# PMIC-MX8M.net
KiCad netlist of a schematic drawn in Altium Designer
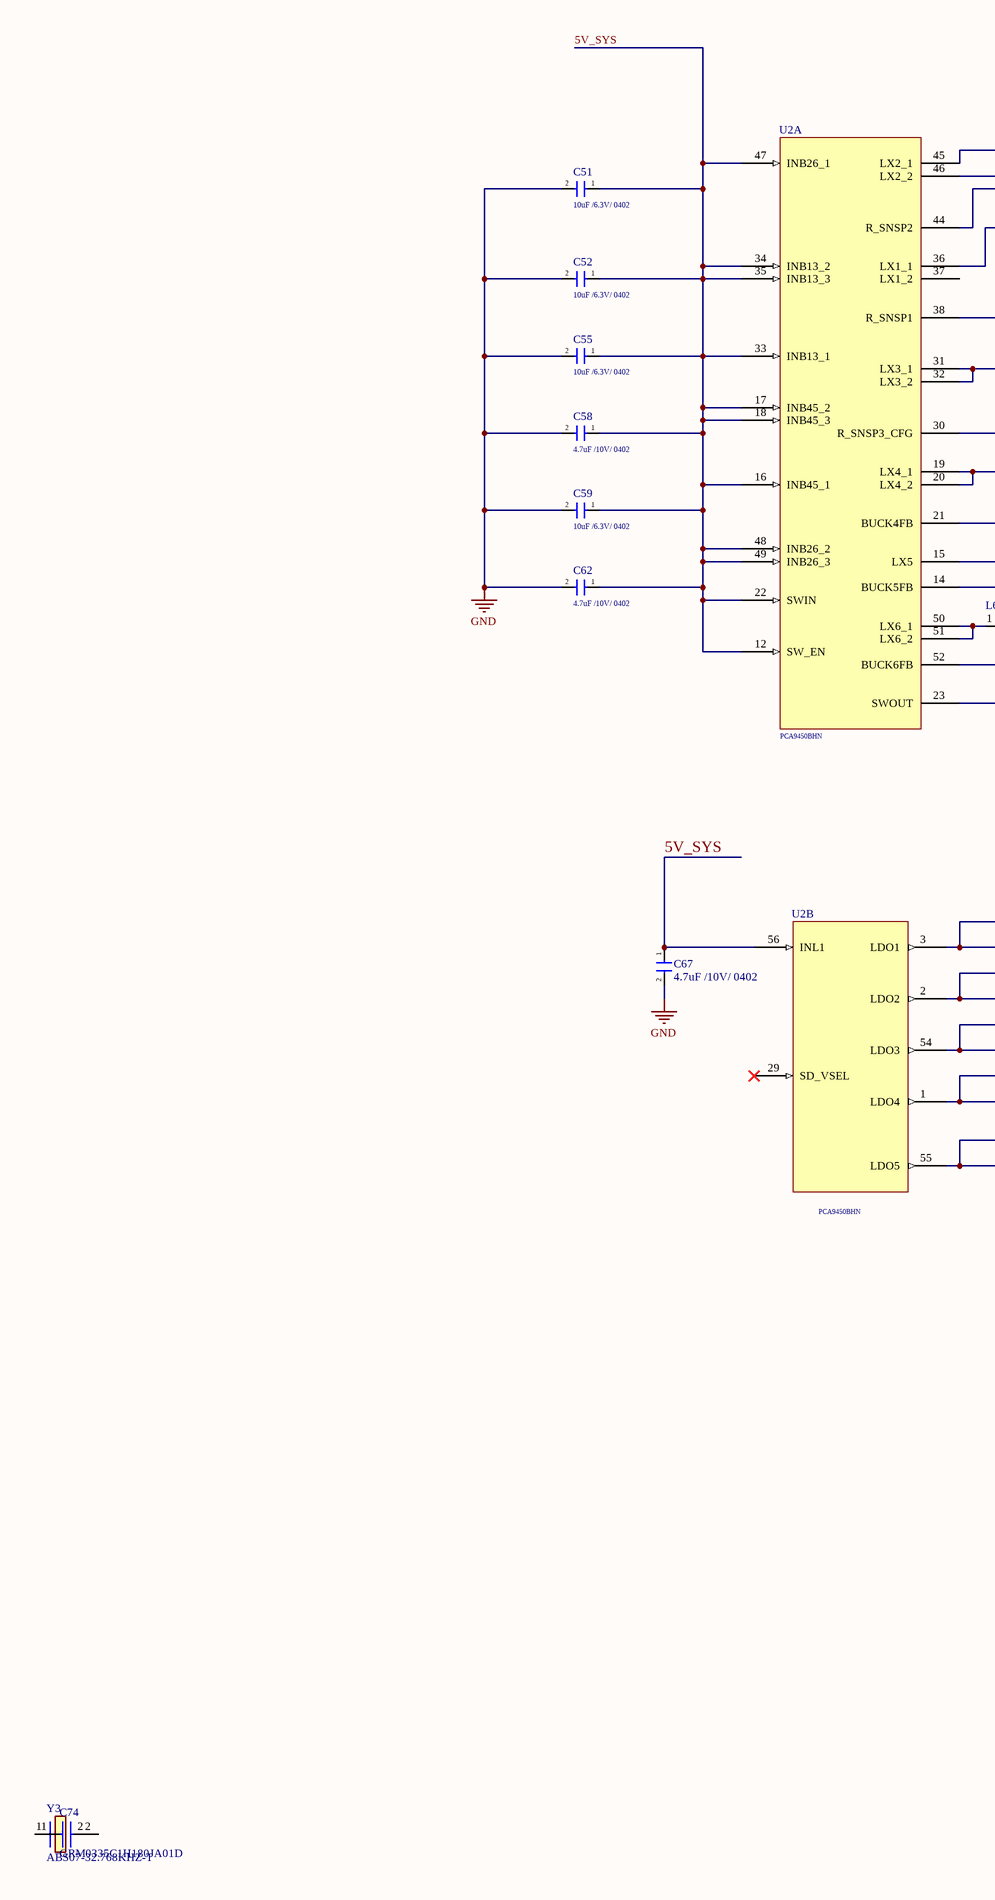
[diagram p0: PMIC-MX8M.SchDoc, left]
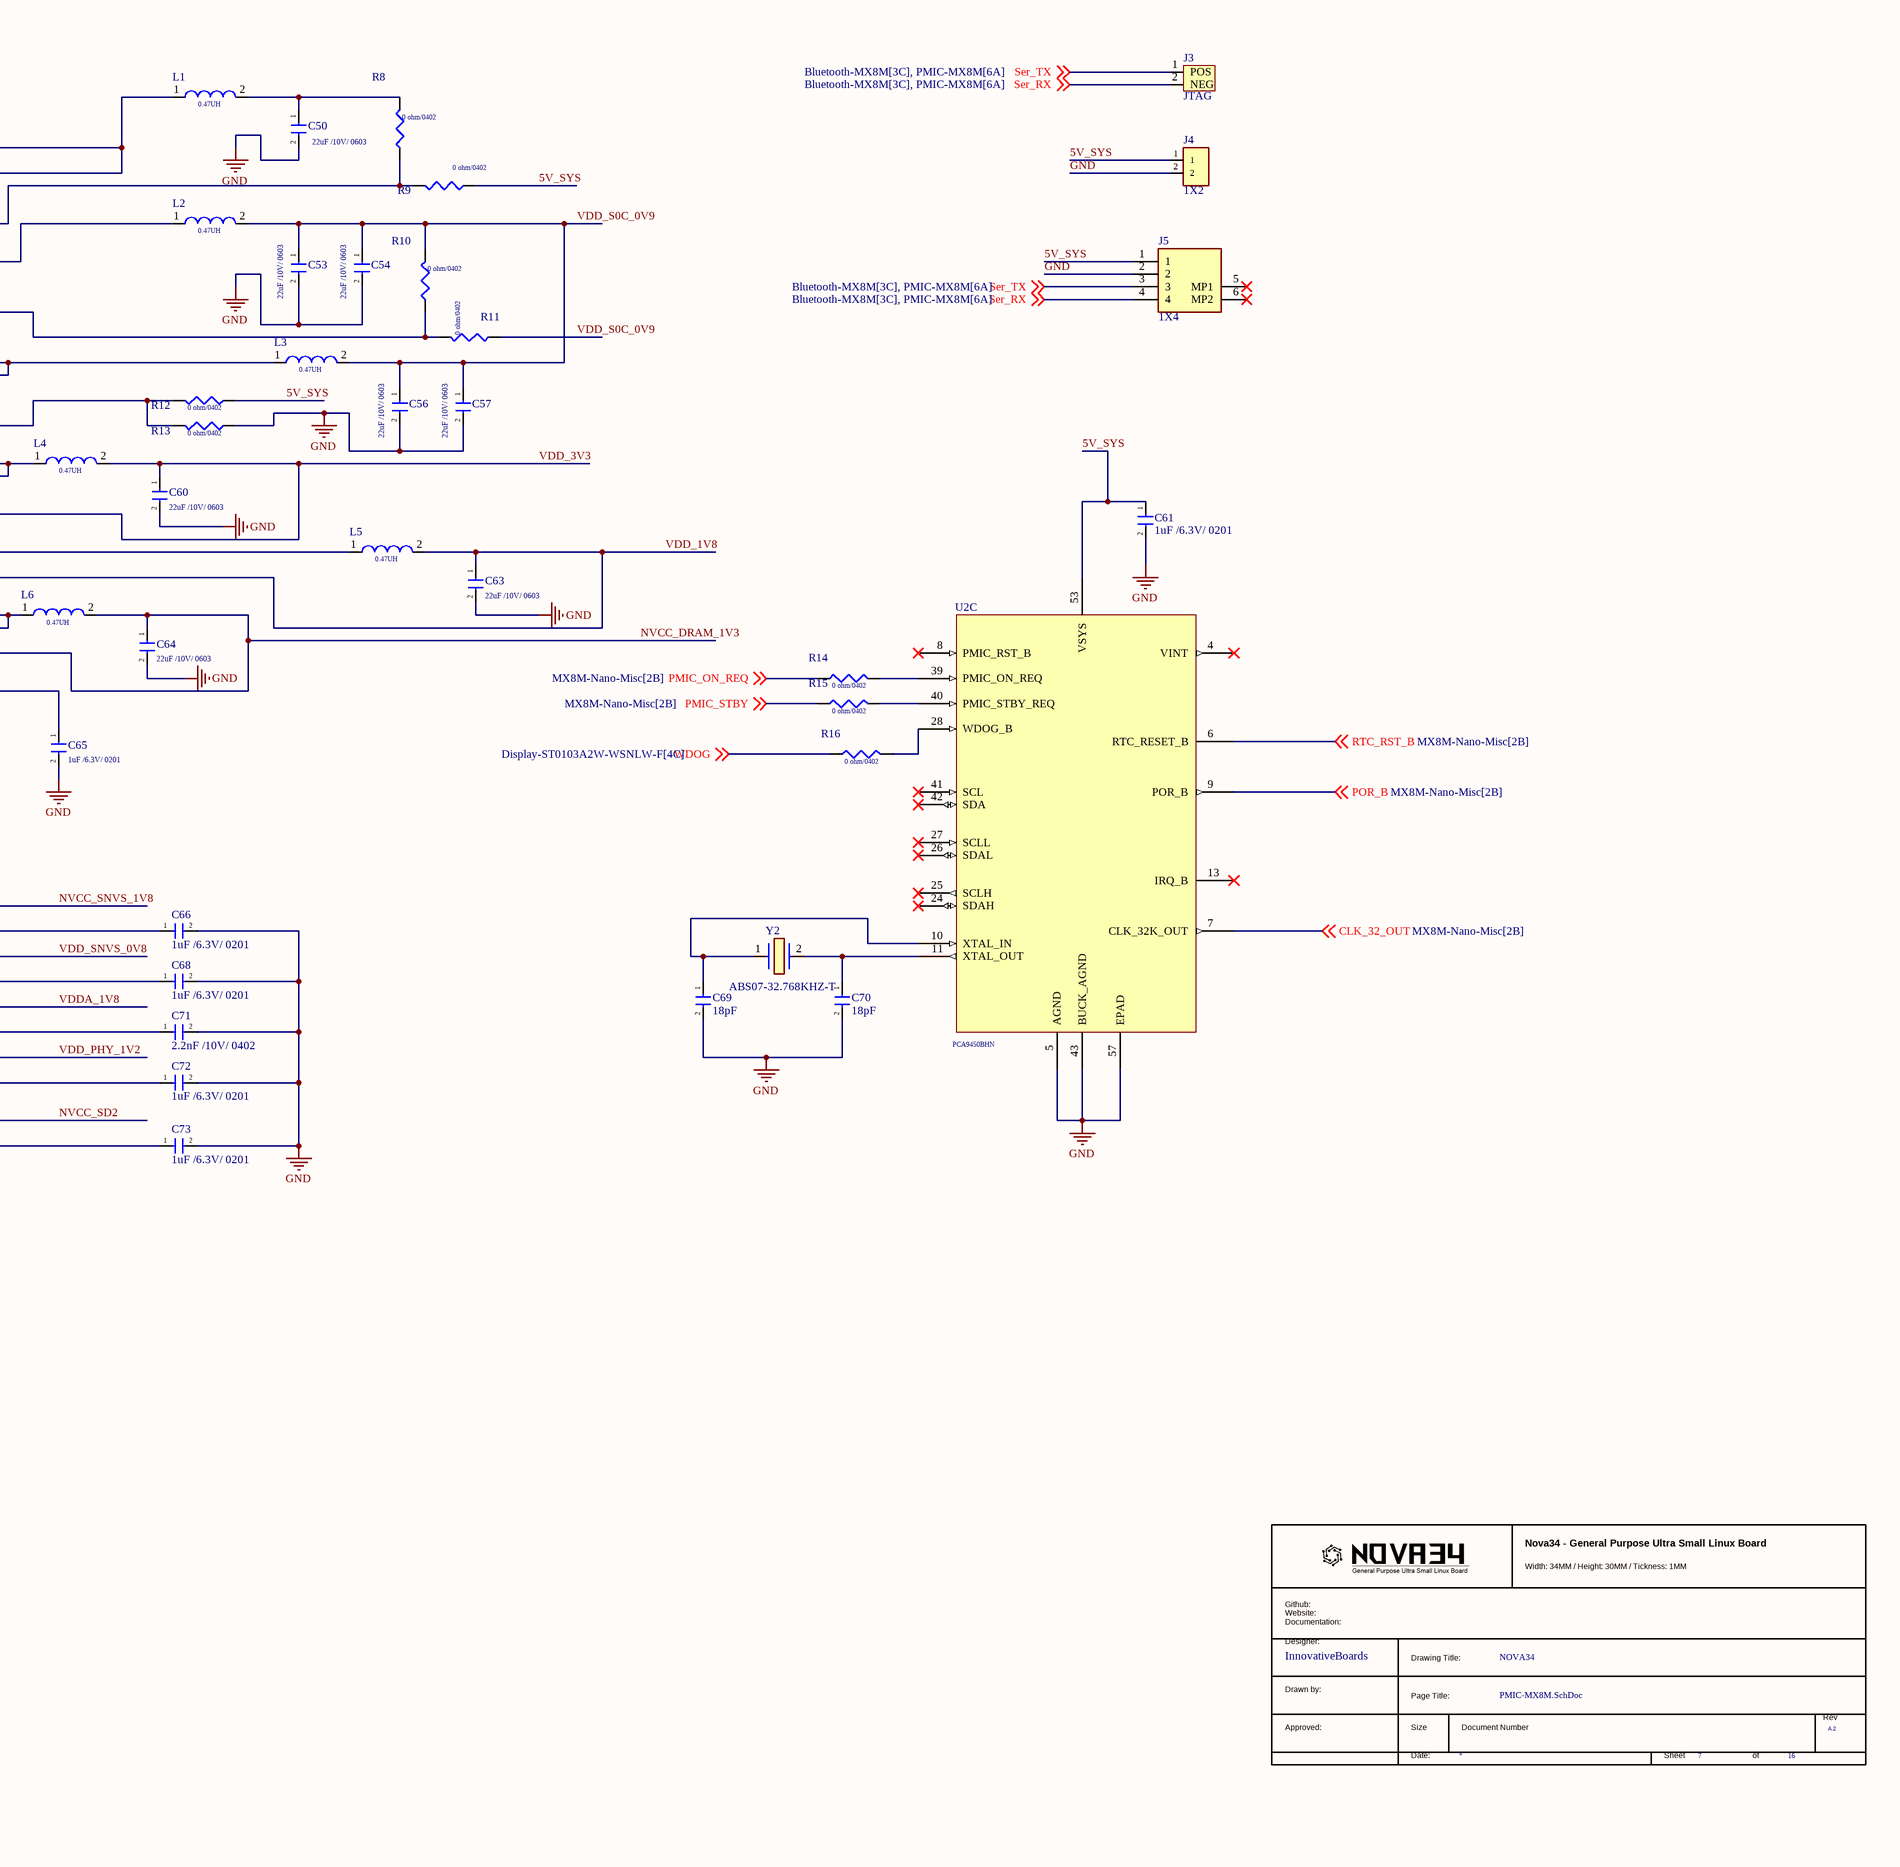
[diagram p1: PMIC-MX8M.SchDoc, right]

(export (version "E")
  (design (tool "Eeschema 10.0.6"))
  (components
    (comp (ref "*")
      (value "TitleBlock_MCPG")
      (fields (field (name "REVCODE") "A.2"))
      (libsource (lib "Nova_SCHLIB") (part "TitleBlock_MCPG"))
    )
    (comp (ref "C50")
      (value "22uF /10V/ 0603")
      (footprint "GRM18x")
      (description "Multilayer Ceramic Capacitors MLCC - SMD/SMT 22 uF 10 VDC 20% 0603 X5R")
      (fields
        (field (name "MANUFACTURER_PART_NUMBER") "GRM187R61A226ME15D")
        (field (name "MOUSER PART NUMBER") "81-GRM187R61A226ME5D")
      )
      (libsource (lib "Nova_SCHLIB") (part "GRM187R61A226ME15D"))
    )
    (comp (ref "C51")
      (value "10uF /6.3V/ 0402")
      (footprint "CAPC1005X65N")
      (description "Multilayer Ceramic Capacitors MLCC - SMD/SMT 10 uF 6.3 VDC 20% 0402 X5R")
      (fields
        (field (name "MANUFACTURER_PART_NUMBER") "GRM155R60J106ME15D")
        (field (name "MOUSER PART NUMBER") "81-GRM155R60J106ME5D")
      )
      (libsource (lib "Nova_SCHLIB") (part "GRM155R60J106ME15D"))
    )
    (comp (ref "C52")
      (value "10uF /6.3V/ 0402")
      (footprint "CAPC1005X65N")
      (description "Multilayer Ceramic Capacitors MLCC - SMD/SMT 10 uF 6.3 VDC 20% 0402 X5R")
      (fields
        (field (name "MANUFACTURER_PART_NUMBER") "GRM155R60J106ME15D")
        (field (name "MOUSER PART NUMBER") "81-GRM155R60J106ME5D")
      )
      (libsource (lib "Nova_SCHLIB") (part "GRM155R60J106ME15D"))
    )
    (comp (ref "C53")
      (value "22uF /10V/ 0603")
      (footprint "GRM18x")
      (description "Multilayer Ceramic Capacitors MLCC - SMD/SMT 22 uF 10 VDC 20% 0603 X5R")
      (fields
        (field (name "MANUFACTURER_PART_NUMBER") "GRM187R61A226ME15D")
        (field (name "MOUSER PART NUMBER") "81-GRM187R61A226ME5D")
      )
      (libsource (lib "Nova_SCHLIB") (part "GRM187R61A226ME15D"))
    )
    (comp (ref "C54")
      (value "22uF /10V/ 0603")
      (footprint "GRM18x")
      (description "Multilayer Ceramic Capacitors MLCC - SMD/SMT 22 uF 10 VDC 20% 0603 X5R")
      (fields
        (field (name "MANUFACTURER_PART_NUMBER") "GRM187R61A226ME15D")
        (field (name "MOUSER PART NUMBER") "81-GRM187R61A226ME5D")
      )
      (libsource (lib "Nova_SCHLIB") (part "GRM187R61A226ME15D"))
    )
    (comp (ref "C55")
      (value "10uF /6.3V/ 0402")
      (footprint "CAPC1005X65N")
      (description "Multilayer Ceramic Capacitors MLCC - SMD/SMT 10 uF 6.3 VDC 20% 0402 X5R")
      (fields
        (field (name "MANUFACTURER_PART_NUMBER") "GRM155R60J106ME15D")
        (field (name "MOUSER PART NUMBER") "81-GRM155R60J106ME5D")
      )
      (libsource (lib "Nova_SCHLIB") (part "GRM155R60J106ME15D"))
    )
    (comp (ref "C56")
      (value "22uF /10V/ 0603")
      (footprint "GRM18x")
      (description "Multilayer Ceramic Capacitors MLCC - SMD/SMT 22 uF 10 VDC 20% 0603 X5R")
      (fields
        (field (name "MANUFACTURER_PART_NUMBER") "GRM187R61A226ME15D")
        (field (name "MOUSER PART NUMBER") "81-GRM187R61A226ME5D")
      )
      (libsource (lib "Nova_SCHLIB") (part "GRM187R61A226ME15D"))
    )
    (comp (ref "C57")
      (value "22uF /10V/ 0603")
      (footprint "GRM18x")
      (description "Multilayer Ceramic Capacitors MLCC - SMD/SMT 22 uF 10 VDC 20% 0603 X5R")
      (fields
        (field (name "MANUFACTURER_PART_NUMBER") "GRM187R61A226ME15D")
        (field (name "MOUSER PART NUMBER") "81-GRM187R61A226ME5D")
      )
      (libsource (lib "Nova_SCHLIB") (part "GRM187R61A226ME15D"))
    )
    (comp (ref "C58")
      (value "4.7uF /10V/ 0402")
      (footprint "CAPC1005X70N")
      (description "Multilayer Ceramic Capacitors MLCC - SMD/SMT 0402 X6S 4.7 F 20 10VDC AEC-Q200")
      (fields
        (field (name "MANUFACTURER_PART_NUMBER") "GRT155C81A475ME13J")
        (field (name "MOUSER PART NUMBER") "81-GRT155C81A475ME3J")
      )
      (libsource (lib "Nova_SCHLIB") (part "GRT155C81A475ME13J"))
    )
    (comp (ref "C59")
      (value "10uF /6.3V/ 0402")
      (footprint "CAPC1005X65N")
      (description "Multilayer Ceramic Capacitors MLCC - SMD/SMT 10 uF 6.3 VDC 20% 0402 X5R")
      (fields
        (field (name "MANUFACTURER_PART_NUMBER") "GRM155R60J106ME15D")
        (field (name "MOUSER PART NUMBER") "81-GRM155R60J106ME5D")
      )
      (libsource (lib "Nova_SCHLIB") (part "GRM155R60J106ME15D"))
    )
    (comp (ref "C60")
      (value "22uF /10V/ 0603")
      (footprint "GRM18x")
      (description "Multilayer Ceramic Capacitors MLCC - SMD/SMT 22 uF 10 VDC 20% 0603 X5R")
      (fields
        (field (name "MANUFACTURER_PART_NUMBER") "GRM187R61A226ME15D")
        (field (name "MOUSER PART NUMBER") "81-GRM187R61A226ME5D")
      )
      (libsource (lib "Nova_SCHLIB") (part "GRM187R61A226ME15D"))
    )
    (comp (ref "C61")
      (value "1uF /6.3V/ 0201")
      (footprint "GRM033D70J224ME01D")
      (description "Multilayer Ceramic Capacitors MLCC - SMD/SMT 1 uF 6.3 VDC 20% 0201 X6S")
      (fields
        (field (name "MANUFACTURER_PART_NUMBER") "GRM033C80J105ME05J")
        (field (name "MOUSER PART NUMBER") "81-GRM033C80J105ME5J")
      )
      (libsource (lib "Nova_SCHLIB") (part "GRM033C80J105ME05J"))
    )
    (comp (ref "C62")
      (value "4.7uF /10V/ 0402")
      (footprint "CAPC1005X70N")
      (description "Multilayer Ceramic Capacitors MLCC - SMD/SMT 0402 X6S 4.7 F 20 10VDC AEC-Q200")
      (fields
        (field (name "MANUFACTURER_PART_NUMBER") "GRT155C81A475ME13J")
        (field (name "MOUSER PART NUMBER") "81-GRT155C81A475ME3J")
      )
      (libsource (lib "Nova_SCHLIB") (part "GRT155C81A475ME13J"))
    )
    (comp (ref "C63")
      (value "22uF /10V/ 0603")
      (footprint "GRM18x")
      (description "Multilayer Ceramic Capacitors MLCC - SMD/SMT 22 uF 10 VDC 20% 0603 X5R")
      (fields
        (field (name "MANUFACTURER_PART_NUMBER") "GRM187R61A226ME15D")
        (field (name "MOUSER PART NUMBER") "81-GRM187R61A226ME5D")
      )
      (libsource (lib "Nova_SCHLIB") (part "GRM187R61A226ME15D"))
    )
    (comp (ref "C64")
      (value "22uF /10V/ 0603")
      (footprint "GRM18x")
      (description "Multilayer Ceramic Capacitors MLCC - SMD/SMT 22 uF 10 VDC 20% 0603 X5R")
      (fields
        (field (name "MANUFACTURER_PART_NUMBER") "GRM187R61A226ME15D")
        (field (name "MOUSER PART NUMBER") "81-GRM187R61A226ME5D")
      )
      (libsource (lib "Nova_SCHLIB") (part "GRM187R61A226ME15D"))
    )
    (comp (ref "C65")
      (value "1uF /6.3V/ 0201")
      (footprint "GRM033D70J224ME01D")
      (description "Multilayer Ceramic Capacitors MLCC - SMD/SMT 1 uF 6.3 VDC 20% 0201 X6S")
      (fields
        (field (name "MANUFACTURER_PART_NUMBER") "GRM033C80J105ME05J")
        (field (name "MOUSER PART NUMBER") "81-GRM033C80J105ME5J")
      )
      (libsource (lib "Nova_SCHLIB") (part "GRM033C80J105ME05J"))
    )
    (comp (ref "C66")
      (value "1uF /6.3V/ 0201")
      (footprint "GRM033D70J224ME01D")
      (description "Multilayer Ceramic Capacitors MLCC - SMD/SMT 1 uF 6.3 VDC 20% 0201 X6S")
      (fields
        (field (name "MANUFACTURER_PART_NUMBER") "GRM033C80J105ME05J")
        (field (name "MOUSER PART NUMBER") "81-GRM033C80J105ME5J")
      )
      (libsource (lib "Nova_SCHLIB") (part "GRM033C80J105ME05J"))
    )
    (comp (ref "C67")
      (value "4.7uF /10V/ 0402")
      (footprint "CAPC1005X70N")
      (description "Multilayer Ceramic Capacitors MLCC - SMD/SMT 0402 X6S 4.7 F 20 10VDC AEC-Q200")
      (fields
        (field (name "MANUFACTURER_PART_NUMBER") "GRT155C81A475ME13J")
        (field (name "MOUSER PART NUMBER") "81-GRT155C81A475ME3J")
      )
      (libsource (lib "Nova_SCHLIB") (part "GRT155C81A475ME13J"))
    )
    (comp (ref "C68")
      (value "1uF /6.3V/ 0201")
      (footprint "GRM033D70J224ME01D")
      (description "Multilayer Ceramic Capacitors MLCC - SMD/SMT 1 uF 6.3 VDC 20% 0201 X6S")
      (fields
        (field (name "MANUFACTURER_PART_NUMBER") "GRM033C80J105ME05J")
        (field (name "MOUSER PART NUMBER") "81-GRM033C80J105ME5J")
      )
      (libsource (lib "Nova_SCHLIB") (part "GRM033C80J105ME05J"))
    )
    (comp (ref "C69")
      (value "18pF")
      (footprint "CAPC0603X33N")
      (description "Capacitor")
      (fields
        (field (name "MANUFACTURER_PART_NUMBER") "GRM0335C1H180JA01D")
        (field (name "MOUSER PART NUMBER") "81-GRM0335C1H180JA1D")
      )
      (libsource (lib "Nova_SCHLIB") (part "GRM0335C1H180JA01D"))
    )
    (comp (ref "C70")
      (value "18pF")
      (footprint "CAPC0603X33N")
      (description "Capacitor")
      (fields
        (field (name "MANUFACTURER_PART_NUMBER") "GRM0335C1H180JA01D")
        (field (name "MOUSER PART NUMBER") "81-GRM0335C1H180JA1D")
      )
      (libsource (lib "Nova_SCHLIB") (part "GRM0335C1H180JA01D"))
    )
    (comp (ref "C71")
      (value "2.2nF /10V/ 0402")
      (footprint "CAPC1005X70N")
      (description "Multilayer Ceramic Capacitors MLCC - SMD/SMT 2200 pF 10 VDC 10% 0402 X5R")
      (fields
        (field (name "MANUFACTURER_PART_NUMBER") "GRM155R61A222KA01D")
        (field (name "MOUSER PART NUMBER") "81-GRM155R61A222KA1D")
      )
      (libsource (lib "Nova_SCHLIB") (part "GRM155R61A222KA01D"))
    )
    (comp (ref "C72")
      (value "1uF /6.3V/ 0201")
      (footprint "GRM033D70J224ME01D")
      (description "Multilayer Ceramic Capacitors MLCC - SMD/SMT 1 uF 6.3 VDC 20% 0201 X6S")
      (fields
        (field (name "MANUFACTURER_PART_NUMBER") "GRM033C80J105ME05J")
        (field (name "MOUSER PART NUMBER") "81-GRM033C80J105ME5J")
      )
      (libsource (lib "Nova_SCHLIB") (part "GRM033C80J105ME05J"))
    )
    (comp (ref "C73")
      (value "1uF /6.3V/ 0201")
      (footprint "GRM033D70J224ME01D")
      (description "Multilayer Ceramic Capacitors MLCC - SMD/SMT 1 uF 6.3 VDC 20% 0201 X6S")
      (fields
        (field (name "MANUFACTURER_PART_NUMBER") "GRM033C80J105ME05J")
        (field (name "MOUSER PART NUMBER") "81-GRM033C80J105ME5J")
      )
      (libsource (lib "Nova_SCHLIB") (part "GRM033C80J105ME05J"))
    )
    (comp (ref "C74")
      (value "GRM0335C1H180JA01D")
      (footprint "SamacSys:CAPC0603X33N")
      (description "Capacitor")
      (fields (field (name "MOUSER PART NUMBER") "81-GRM0335C1H180JA1D"))
      (libsource (lib "*") (part "GRM0335C1H180JA01D"))
    )
    (comp (ref "J3") (value "JTAG") (footprint "JTAG") (libsource (lib "Nova_SCHLIB") (part "JTAG")))
    (comp (ref "J4")
      (value "1X2")
      (footprint "HDRV2W64P0X254_1X2_508X254X838P")
      (description "Connector")
      (fields
        (field (name "MANUFACTURER_PART_NUMBER") "TSW-102-07-G-S-002")
        (field (name "MOUSER PART NUMBER") "200-TSW-10207GS002")
      )
      (libsource (lib "Nova_SCHLIB") (part "TSW-102-07-G-S-002"))
    )
    (comp (ref "J5")
      (value "1X4")
      (footprint "B4BZRSM4TFLFSN")
      (description "Connector")
      (fields (field (name "MANUFACTURER_PART_NUMBER") "B4B-ZR-SM4-TF(LF)(SN)"))
      (libsource (lib "Nova_SCHLIB") (part "B4B-ZR-SM4-TF_LF__SN_"))
    )
    (comp (ref "L1")
      (value "0.47UH")
      (footprint "IND_SPH2520")
      (description "470 nH Shielded Drum Core, Wirewound Inductor 4.1 A 32mOhm Max 1008 (2520 Metric)")
      (fields (field (name "TOLERANCE") "20%"))
      (libsource (lib "Nova_SCHLIB") (part "WPN252012ER47MT"))
    )
    (comp (ref "L2")
      (value "0.47UH")
      (footprint "IND_SPH2520")
      (description "470 nH Shielded Drum Core, Wirewound Inductor 4.1 A 32mOhm Max 1008 (2520 Metric)")
      (fields (field (name "TOLERANCE") "20%"))
      (libsource (lib "Nova_SCHLIB") (part "WPN252012ER47MT"))
    )
    (comp (ref "L3")
      (value "0.47UH")
      (footprint "IND_SPH2520")
      (description "470 nH Shielded Drum Core, Wirewound Inductor 4.1 A 32mOhm Max 1008 (2520 Metric)")
      (fields (field (name "TOLERANCE") "20%"))
      (libsource (lib "Nova_SCHLIB") (part "WPN252012ER47MT"))
    )
    (comp (ref "L4")
      (value "0.47UH")
      (footprint "IND_SPH2520")
      (description "470 nH Shielded Drum Core, Wirewound Inductor 4.1 A 32mOhm Max 1008 (2520 Metric)")
      (fields (field (name "TOLERANCE") "20%"))
      (libsource (lib "Nova_SCHLIB") (part "WPN252012ER47MT"))
    )
    (comp (ref "L5")
      (value "0.47UH")
      (footprint "IND_SPH2520")
      (description "470 nH Shielded Drum Core, Wirewound Inductor 4.1 A 32mOhm Max 1008 (2520 Metric)")
      (fields (field (name "TOLERANCE") "20%"))
      (libsource (lib "Nova_SCHLIB") (part "WPN252012ER47MT"))
    )
    (comp (ref "L6")
      (value "0.47UH")
      (footprint "IND_SPH2520")
      (description "470 nH Shielded Drum Core, Wirewound Inductor 4.1 A 32mOhm Max 1008 (2520 Metric)")
      (fields (field (name "TOLERANCE") "20%"))
      (libsource (lib "Nova_SCHLIB") (part "WPN252012ER47MT"))
    )
    (comp (ref "R8")
      (value "0 ohm/0402")
      (footprint "RES_0402")
      (description "RES MF ZERO OHM 1/16W 5% 0402")
      (fields (field (name "TOLERANCE") "5%") (field (name "VOLTAGE") "1/16W"))
      (libsource (lib "Nova_SCHLIB") (part "RC0402JR-070RL"))
    )
    (comp (ref "R9")
      (value "0 ohm/0402")
      (footprint "RES_0402")
      (description "RES MF ZERO OHM 1/16W 5% 0402")
      (fields (field (name "TOLERANCE") "5%") (field (name "VOLTAGE") "1/16W"))
      (libsource (lib "Nova_SCHLIB") (part "RC0402JR-070RL"))
    )
    (comp (ref "R10")
      (value "0 ohm/0402")
      (footprint "RES_0402")
      (description "RES MF ZERO OHM 1/16W 5% 0402")
      (fields (field (name "TOLERANCE") "5%") (field (name "VOLTAGE") "1/16W"))
      (libsource (lib "Nova_SCHLIB") (part "RC0402JR-070RL"))
    )
    (comp (ref "R11")
      (value "0 ohm/0402")
      (footprint "RES_0402")
      (description "RES MF ZERO OHM 1/16W 5% 0402")
      (fields (field (name "TOLERANCE") "5%") (field (name "VOLTAGE") "1/16W"))
      (libsource (lib "Nova_SCHLIB") (part "RC0402JR-070RL"))
    )
    (comp (ref "R12")
      (value "0 ohm/0402")
      (footprint "RES_0402")
      (description "RES MF ZERO OHM 1/16W 5% 0402")
      (fields (field (name "TOLERANCE") "5%") (field (name "VOLTAGE") "1/16W"))
      (libsource (lib "Nova_SCHLIB") (part "RC0402JR-070RL"))
    )
    (comp (ref "R13")
      (value "0 ohm/0402")
      (footprint "RES_0402")
      (description "RES MF ZERO OHM 1/16W 5% 0402")
      (fields (field (name "TOLERANCE") "5%") (field (name "VOLTAGE") "1/16W"))
      (libsource (lib "Nova_SCHLIB") (part "RC0402JR-070RL"))
    )
    (comp (ref "R14")
      (value "0 ohm/0402")
      (footprint "RES_0402")
      (description "RES MF ZERO OHM 1/16W 5% 0402")
      (fields (field (name "TOLERANCE") "5%") (field (name "VOLTAGE") "1/16W"))
      (libsource (lib "Nova_SCHLIB") (part "RC0402JR-070RL"))
    )
    (comp (ref "R15")
      (value "0 ohm/0402")
      (footprint "RES_0402")
      (description "RES MF ZERO OHM 1/16W 5% 0402")
      (fields (field (name "TOLERANCE") "5%") (field (name "VOLTAGE") "1/16W"))
      (libsource (lib "Nova_SCHLIB") (part "RC0402JR-070RL"))
    )
    (comp (ref "R16")
      (value "0 ohm/0402")
      (footprint "RES_0402")
      (description "RES MF ZERO OHM 1/16W 5% 0402")
      (fields (field (name "TOLERANCE") "5%") (field (name "VOLTAGE") "1/16W"))
      (libsource (lib "Nova_SCHLIB") (part "RC0402JR-070RL"))
    )
    (comp (ref "U2")
      (value "PCA9450BHN")
      (footprint "QFN40P700X700X100-57N-D")
      (description "IC POWER MANAGEMENT 2.7-5.5V HVQFN56")
      (fields (field (name "VOLTAGE") "2.7-5.5V"))
      (libsource (lib "Nova_SCHLIB") (part "PCA9450_HVQFN56P_A"))
    )
    (comp (ref "Y2")
      (value "ABS07-32.768KHZ-T")
      (footprint "ABS07")
      (description "Crystal or Oscillator")
      (fields (field (name "MOUSER PART NUMBER") "815-ABS07-32.768KHZT"))
      (libsource (lib "Nova_SCHLIB") (part "ABS07-32.768KHZ-T"))
    )
    (comp (ref "Y3")
      (value "ABS07-32.768KHZ-T")
      (footprint "SamacSys:ABS07")
      (description "Crystal or Oscillator")
      (fields (field (name "MOUSER PART NUMBER") "815-ABS07-32.768KHZT"))
      (libsource (lib "*") (part "ABS07-32.768KHZ-T"))
    )
  )
  (nets
    (net (code "1") (name "/5V_SYS") (class "Default")
      (node (ref "C51") (pin "1") (pinfunction "1_1") (pintype "passive"))
      (node (ref "C52") (pin "1") (pinfunction "1_1") (pintype "passive"))
      (node (ref "C55") (pin "1") (pinfunction "1_1") (pintype "passive"))
      (node (ref "C58") (pin "1") (pinfunction "1_1") (pintype "passive"))
      (node (ref "C59") (pin "1") (pinfunction "1_1") (pintype "passive"))
      (node (ref "C61") (pin "1") (pinfunction "1_1") (pintype "passive"))
      (node (ref "C62") (pin "1") (pinfunction "1_1") (pintype "passive"))
      (node (ref "C67") (pin "1") (pinfunction "1_1") (pintype "passive"))
      (node (ref "J4") (pin "1") (pinfunction "1_1") (pintype "passive"))
      (node (ref "J5") (pin "1") (pinfunction "1_1") (pintype "passive"))
      (node (ref "R12") (pin "1") (pinfunction "1_1") (pintype "passive"))
      (node (ref "R9") (pin "1") (pinfunction "1_1") (pintype "passive"))
      (node (ref "U2") (pin "12") (pinfunction "SW_EN_12") (pintype "input"))
      (node (ref "U2") (pin "16") (pinfunction "INB45_1_16") (pintype "input"))
      (node (ref "U2") (pin "17") (pinfunction "INB45_2_17") (pintype "input"))
      (node (ref "U2") (pin "18") (pinfunction "INB45_3_18") (pintype "input"))
      (node (ref "U2") (pin "22") (pinfunction "SWIN_22") (pintype "input"))
      (node (ref "U2") (pin "33") (pinfunction "INB13_1_33") (pintype "input"))
      (node (ref "U2") (pin "34") (pinfunction "INB13_2_34") (pintype "input"))
      (node (ref "U2") (pin "35") (pinfunction "INB13_3_35") (pintype "input"))
      (node (ref "U2") (pin "47") (pinfunction "INB26_1_47") (pintype "input"))
      (node (ref "U2") (pin "48") (pinfunction "INB26_2_48") (pintype "input"))
      (node (ref "U2") (pin "49") (pinfunction "INB26_3_49") (pintype "input"))
      (node (ref "U2") (pin "53") (pinfunction "VSYS_53") (pintype "power_in"))
      (node (ref "U2") (pin "56") (pinfunction "INL1_56") (pintype "input"))
    )
    (net (code "2") (name "/NVCC_DRAM_1V3") (class "Default")
      (node (ref "C64") (pin "1") (pinfunction "1_1") (pintype "passive"))
      (node (ref "L6") (pin "2") (pinfunction "2_2") (pintype "passive"))
      (node (ref "U2") (pin "52") (pinfunction "BUCK6FB_52") (pintype "passive"))
    )
    (net (code "3") (name "/NVCC_SD2") (class "Default")
      (node (ref "C73") (pin "1") (pinfunction "1_1") (pintype "passive"))
      (node (ref "U2") (pin "55") (pinfunction "LDO5_55") (pintype "output"))
    )
    (net (code "4") (name "/NVCC_SNVS_1V8") (class "Default")
      (node (ref "C66") (pin "1") (pinfunction "1_1") (pintype "passive"))
      (node (ref "U2") (pin "3") (pinfunction "LDO1_3") (pintype "output"))
    )
    (net (code "5") (name "/VDDA_1V8") (class "Default")
      (node (ref "C71") (pin "1") (pinfunction "1_1") (pintype "passive"))
      (node (ref "U2") (pin "54") (pinfunction "LDO3_54") (pintype "output"))
    )
    (net (code "6") (name "/VDD_1V8") (class "Default")
      (node (ref "C63") (pin "1") (pinfunction "1_1") (pintype "passive"))
      (node (ref "L5") (pin "2") (pinfunction "2_2") (pintype "passive"))
      (node (ref "U2") (pin "14") (pinfunction "BUCK5FB_14") (pintype "passive"))
    )
    (net (code "7") (name "/VDD_3V3") (class "Default")
      (node (ref "C60") (pin "1") (pinfunction "1_1") (pintype "passive"))
      (node (ref "L4") (pin "2") (pinfunction "2_2") (pintype "passive"))
      (node (ref "U2") (pin "21") (pinfunction "BUCK4FB_21") (pintype "passive"))
    )
    (net (code "8") (name "/VDD_PHY_1V2") (class "Default")
      (node (ref "C72") (pin "1") (pinfunction "1_1") (pintype "passive"))
      (node (ref "U2") (pin "1") (pinfunction "LDO4_1") (pintype "output"))
    )
    (net (code "9") (name "/VDD_S0C_0V9") (class "Default")
      (node (ref "C53") (pin "1") (pinfunction "1_1") (pintype "passive"))
      (node (ref "C54") (pin "1") (pinfunction "1_1") (pintype "passive"))
      (node (ref "C56") (pin "1") (pinfunction "1_1") (pintype "passive"))
      (node (ref "C57") (pin "1") (pinfunction "1_1") (pintype "passive"))
      (node (ref "L2") (pin "2") (pinfunction "2_2") (pintype "passive"))
      (node (ref "L3") (pin "2") (pinfunction "2_2") (pintype "passive"))
      (node (ref "R10") (pin "2") (pinfunction "2_2") (pintype "passive"))
      (node (ref "R11") (pin "1") (pinfunction "1_1") (pintype "passive"))
    )
    (net (code "10") (name "/VDD_SNVS_0V8") (class "Default")
      (node (ref "C68") (pin "1") (pinfunction "1_1") (pintype "passive"))
      (node (ref "U2") (pin "2") (pinfunction "LDO2_2") (pintype "output"))
    )
    (net (code "11") (name "CLK_32_OUT") (class "Default")
      (node (ref "U2") (pin "7") (pinfunction "CLK_32K_OUT_7") (pintype "output"))
    )
    (net (code "12") (name "GND") (class "Default")
      (node (ref "C50") (pin "2") (pinfunction "2_2") (pintype "passive"))
      (node (ref "C51") (pin "2") (pinfunction "2_2") (pintype "passive"))
      (node (ref "C52") (pin "2") (pinfunction "2_2") (pintype "passive"))
      (node (ref "C53") (pin "2") (pinfunction "2_2") (pintype "passive"))
      (node (ref "C54") (pin "2") (pinfunction "2_2") (pintype "passive"))
      (node (ref "C55") (pin "2") (pinfunction "2_2") (pintype "passive"))
      (node (ref "C56") (pin "2") (pinfunction "2_2") (pintype "passive"))
      (node (ref "C57") (pin "2") (pinfunction "2_2") (pintype "passive"))
      (node (ref "C58") (pin "2") (pinfunction "2_2") (pintype "passive"))
      (node (ref "C59") (pin "2") (pinfunction "2_2") (pintype "passive"))
      (node (ref "C60") (pin "2") (pinfunction "2_2") (pintype "passive"))
      (node (ref "C61") (pin "2") (pinfunction "2_2") (pintype "passive"))
      (node (ref "C62") (pin "2") (pinfunction "2_2") (pintype "passive"))
      (node (ref "C63") (pin "2") (pinfunction "2_2") (pintype "passive"))
      (node (ref "C64") (pin "2") (pinfunction "2_2") (pintype "passive"))
      (node (ref "C65") (pin "2") (pinfunction "2_2") (pintype "passive"))
      (node (ref "C66") (pin "2") (pinfunction "2_2") (pintype "passive"))
      (node (ref "C67") (pin "2") (pinfunction "2_2") (pintype "passive"))
      (node (ref "C68") (pin "2") (pinfunction "2_2") (pintype "passive"))
      (node (ref "C69") (pin "2") (pinfunction "2_2") (pintype "passive"))
      (node (ref "C70") (pin "2") (pinfunction "2_2") (pintype "passive"))
      (node (ref "C71") (pin "2") (pinfunction "2_2") (pintype "passive"))
      (node (ref "C72") (pin "2") (pinfunction "2_2") (pintype "passive"))
      (node (ref "C73") (pin "2") (pinfunction "2_2") (pintype "passive"))
      (node (ref "J4") (pin "2") (pinfunction "2_2") (pintype "passive"))
      (node (ref "J5") (pin "2") (pinfunction "2_2") (pintype "passive"))
      (node (ref "R13") (pin "1") (pinfunction "1_1") (pintype "passive"))
      (node (ref "U2") (pin "43") (pinfunction "BUCK_AGND_43") (pintype "power_in"))
      (node (ref "U2") (pin "5") (pinfunction "AGND_5") (pintype "power_in"))
      (node (ref "U2") (pin "57") (pinfunction "EPAD_57") (pintype "power_in"))
    )
    (net (code "13") (name "Net-(C50-Pad1)") (class "Default")
      (node (ref "C50") (pin "1") (pinfunction "1_1") (pintype "passive"))
      (node (ref "L1") (pin "2") (pinfunction "2_2") (pintype "passive"))
      (node (ref "R8") (pin "2") (pinfunction "2_2") (pintype "passive"))
    )
    (net (code "14") (name "Net-(C74-Pad1)") (class "Default")
      (node (ref "C74") (pin "1") (pinfunction "1_1") (pintype "passive"))
      (node (ref "Y3") (pin "1") (pinfunction "1_1") (pintype "passive"))
    )
    (net (code "15") (name "Net-(U2A-LX1_1)") (class "Default")
      (node (ref "L2") (pin "1") (pinfunction "1_1") (pintype "passive"))
      (node (ref "U2") (pin "36") (pinfunction "LX1_1_36") (pintype "passive"))
    )
    (net (code "16") (name "Net-(U2A-LX2_1)") (class "Default")
      (node (ref "L1") (pin "1") (pinfunction "1_1") (pintype "passive"))
      (node (ref "U2") (pin "45") (pinfunction "LX2_1_45") (pintype "passive"))
      (node (ref "U2") (pin "46") (pinfunction "LX2_2_46") (pintype "passive"))
    )
    (net (code "17") (name "Net-(U2A-LX3_1)") (class "Default")
      (node (ref "L3") (pin "1") (pinfunction "1_1") (pintype "passive"))
      (node (ref "U2") (pin "31") (pinfunction "LX3_1_31") (pintype "passive"))
      (node (ref "U2") (pin "32") (pinfunction "LX3_2_32") (pintype "passive"))
    )
    (net (code "18") (name "Net-(U2A-LX4_1)") (class "Default")
      (node (ref "L4") (pin "1") (pinfunction "1_1") (pintype "passive"))
      (node (ref "U2") (pin "19") (pinfunction "LX4_1_19") (pintype "passive"))
      (node (ref "U2") (pin "20") (pinfunction "LX4_2_20") (pintype "passive"))
    )
    (net (code "19") (name "Net-(U2A-LX5)") (class "Default")
      (node (ref "L5") (pin "1") (pinfunction "1_1") (pintype "passive"))
      (node (ref "U2") (pin "15") (pinfunction "LX5_15") (pintype "passive"))
    )
    (net (code "20") (name "Net-(U2A-LX6_1)") (class "Default")
      (node (ref "L6") (pin "1") (pinfunction "1_1") (pintype "passive"))
      (node (ref "U2") (pin "50") (pinfunction "LX6_1_50") (pintype "passive"))
      (node (ref "U2") (pin "51") (pinfunction "LX6_2_51") (pintype "passive"))
    )
    (net (code "21") (name "Net-(U2A-R_SNSP1)") (class "Default")
      (node (ref "R10") (pin "1") (pinfunction "1_1") (pintype "passive"))
      (node (ref "R11") (pin "2") (pinfunction "2_2") (pintype "passive"))
      (node (ref "U2") (pin "38") (pinfunction "R_SNSP1_38") (pintype "passive"))
    )
    (net (code "22") (name "Net-(U2A-R_SNSP2)") (class "Default")
      (node (ref "R8") (pin "1") (pinfunction "1_1") (pintype "passive"))
      (node (ref "R9") (pin "2") (pinfunction "2_2") (pintype "passive"))
      (node (ref "U2") (pin "44") (pinfunction "R_SNSP2_44") (pintype "passive"))
    )
    (net (code "23") (name "Net-(U2A-R_SNSP3_CFG)") (class "Default")
      (node (ref "R12") (pin "2") (pinfunction "2_2") (pintype "passive"))
      (node (ref "R13") (pin "2") (pinfunction "2_2") (pintype "passive"))
      (node (ref "U2") (pin "30") (pinfunction "R_SNSP3_CFG_30") (pintype "passive"))
    )
    (net (code "24") (name "Net-(U2A-SWOUT)") (class "Default")
      (node (ref "C65") (pin "1") (pinfunction "1_1") (pintype "passive"))
      (node (ref "U2") (pin "23") (pinfunction "SWOUT_23") (pintype "passive"))
    )
    (net (code "25") (name "Net-(U2C-PMIC_ON_REQ)") (class "Default")
      (node (ref "R14") (pin "2") (pinfunction "2_2") (pintype "passive"))
      (node (ref "U2") (pin "39") (pinfunction "PMIC_ON_REQ_39") (pintype "input"))
    )
    (net (code "26") (name "Net-(U2C-PMIC_STBY_REQ)") (class "Default")
      (node (ref "R15") (pin "2") (pinfunction "2_2") (pintype "passive"))
      (node (ref "U2") (pin "40") (pinfunction "PMIC_STBY_REQ_40") (pintype "input"))
    )
    (net (code "27") (name "Net-(U2C-WDOG_B)") (class "Default")
      (node (ref "R16") (pin "2") (pinfunction "2_2") (pintype "passive"))
      (node (ref "U2") (pin "28") (pinfunction "WDOG_B_28") (pintype "input"))
    )
    (net (code "28") (name "Net-(U2C-XTAL_IN)") (class "Default")
      (node (ref "C69") (pin "1") (pinfunction "1_1") (pintype "passive"))
      (node (ref "U2") (pin "10") (pinfunction "XTAL_IN_10") (pintype "input"))
      (node (ref "Y2") (pin "1") (pinfunction "1_1") (pintype "passive"))
    )
    (net (code "29") (name "Net-(U2C-XTAL_OUT)") (class "Default")
      (node (ref "C70") (pin "1") (pinfunction "1_1") (pintype "passive"))
      (node (ref "U2") (pin "11") (pinfunction "XTAL_OUT_11") (pintype "output"))
      (node (ref "Y2") (pin "2") (pinfunction "2_2") (pintype "passive"))
    )
    (net (code "30") (name "PMIC_ON_REQ") (class "Default")
      (node (ref "R14") (pin "1") (pinfunction "1_1") (pintype "passive"))
    )
    (net (code "31") (name "PMIC_STBY") (class "Default")
      (node (ref "R15") (pin "1") (pinfunction "1_1") (pintype "passive"))
    )
    (net (code "32") (name "POR_B") (class "Default")
      (node (ref "U2") (pin "9") (pinfunction "POR_B_9") (pintype "output"))
    )
    (net (code "33") (name "RTC_RST_B") (class "Default")
      (node (ref "U2") (pin "6") (pinfunction "RTC_RESET_B_6") (pintype "open_collector"))
    )
    (net (code "34") (name "Ser_RX") (class "Default")
      (node (ref "J3") (pin "2") (pinfunction "NEG_2") (pintype "passive"))
      (node (ref "J5") (pin "4") (pinfunction "4_4") (pintype "passive"))
    )
    (net (code "35") (name "Ser_TX") (class "Default")
      (node (ref "J3") (pin "1") (pinfunction "POS_1") (pintype "passive"))
      (node (ref "J5") (pin "3") (pinfunction "3_3") (pintype "passive"))
    )
    (net (code "36") (name "WDOG") (class "Default")
      (node (ref "R16") (pin "1") (pinfunction "1_1") (pintype "passive"))
    )
    (net (code "37") (name "unconnected-(C74-Pad2)") (class "Default")
      (node (ref "C74") (pin "2") (pinfunction "2_2") (pintype "passive"))
    )
    (net (code "38") (name "unconnected-(J5-MP1-Pad5)") (class "Default")
      (node (ref "J5") (pin "5") (pinfunction "MP1_5") (pintype "passive+no_connect"))
    )
    (net (code "39") (name "unconnected-(J5-MP2-Pad6)") (class "Default")
      (node (ref "J5") (pin "6") (pinfunction "MP2_6") (pintype "passive+no_connect"))
    )
    (net (code "40") (name "unconnected-(U2A-LX1_2-Pad37)") (class "Default")
      (node (ref "U2") (pin "37") (pinfunction "LX1_2_37") (pintype "passive"))
    )
    (net (code "41") (name "unconnected-(U2B-SD_VSEL-Pad29)") (class "Default")
      (node (ref "U2") (pin "29") (pinfunction "SD_VSEL_29") (pintype "input+no_connect"))
    )
    (net (code "42") (name "unconnected-(U2C-IRQ_B-Pad13)") (class "Default")
      (node (ref "U2") (pin "13") (pinfunction "IRQ_B_13") (pintype "open_collector+no_connect"))
    )
    (net (code "43") (name "unconnected-(U2C-PMIC_RST_B-Pad8)") (class "Default")
      (node (ref "U2") (pin "8") (pinfunction "PMIC_RST_B_8") (pintype "input+no_connect"))
    )
    (net (code "44") (name "unconnected-(U2C-SCL-Pad41)") (class "Default")
      (node (ref "U2") (pin "41") (pinfunction "SCL_41") (pintype "input+no_connect"))
    )
    (net (code "45") (name "unconnected-(U2C-SCLH-Pad25)") (class "Default")
      (node (ref "U2") (pin "25") (pinfunction "SCLH_25") (pintype "output+no_connect"))
    )
    (net (code "46") (name "unconnected-(U2C-SCLL-Pad27)") (class "Default")
      (node (ref "U2") (pin "27") (pinfunction "SCLL_27") (pintype "input+no_connect"))
    )
    (net (code "47") (name "unconnected-(U2C-SDA-Pad42)") (class "Default")
      (node (ref "U2") (pin "42") (pinfunction "SDA_42") (pintype "bidirectional+no_connect"))
    )
    (net (code "48") (name "unconnected-(U2C-SDAH-Pad24)") (class "Default")
      (node (ref "U2") (pin "24") (pinfunction "SDAH_24") (pintype "bidirectional+no_connect"))
    )
    (net (code "49") (name "unconnected-(U2C-SDAL-Pad26)") (class "Default")
      (node (ref "U2") (pin "26") (pinfunction "SDAL_26") (pintype "bidirectional+no_connect"))
    )
    (net (code "50") (name "unconnected-(U2C-VINT-Pad4)") (class "Default")
      (node (ref "U2") (pin "4") (pinfunction "VINT_4") (pintype "output+no_connect"))
    )
    (net (code "51") (name "unconnected-(Y3-Pad2)") (class "Default")
      (node (ref "Y3") (pin "2") (pinfunction "2_2") (pintype "passive"))
    )
  )
)
